# Microcontroller.net
KiCad netlist of a schematic drawn in Altium Designer
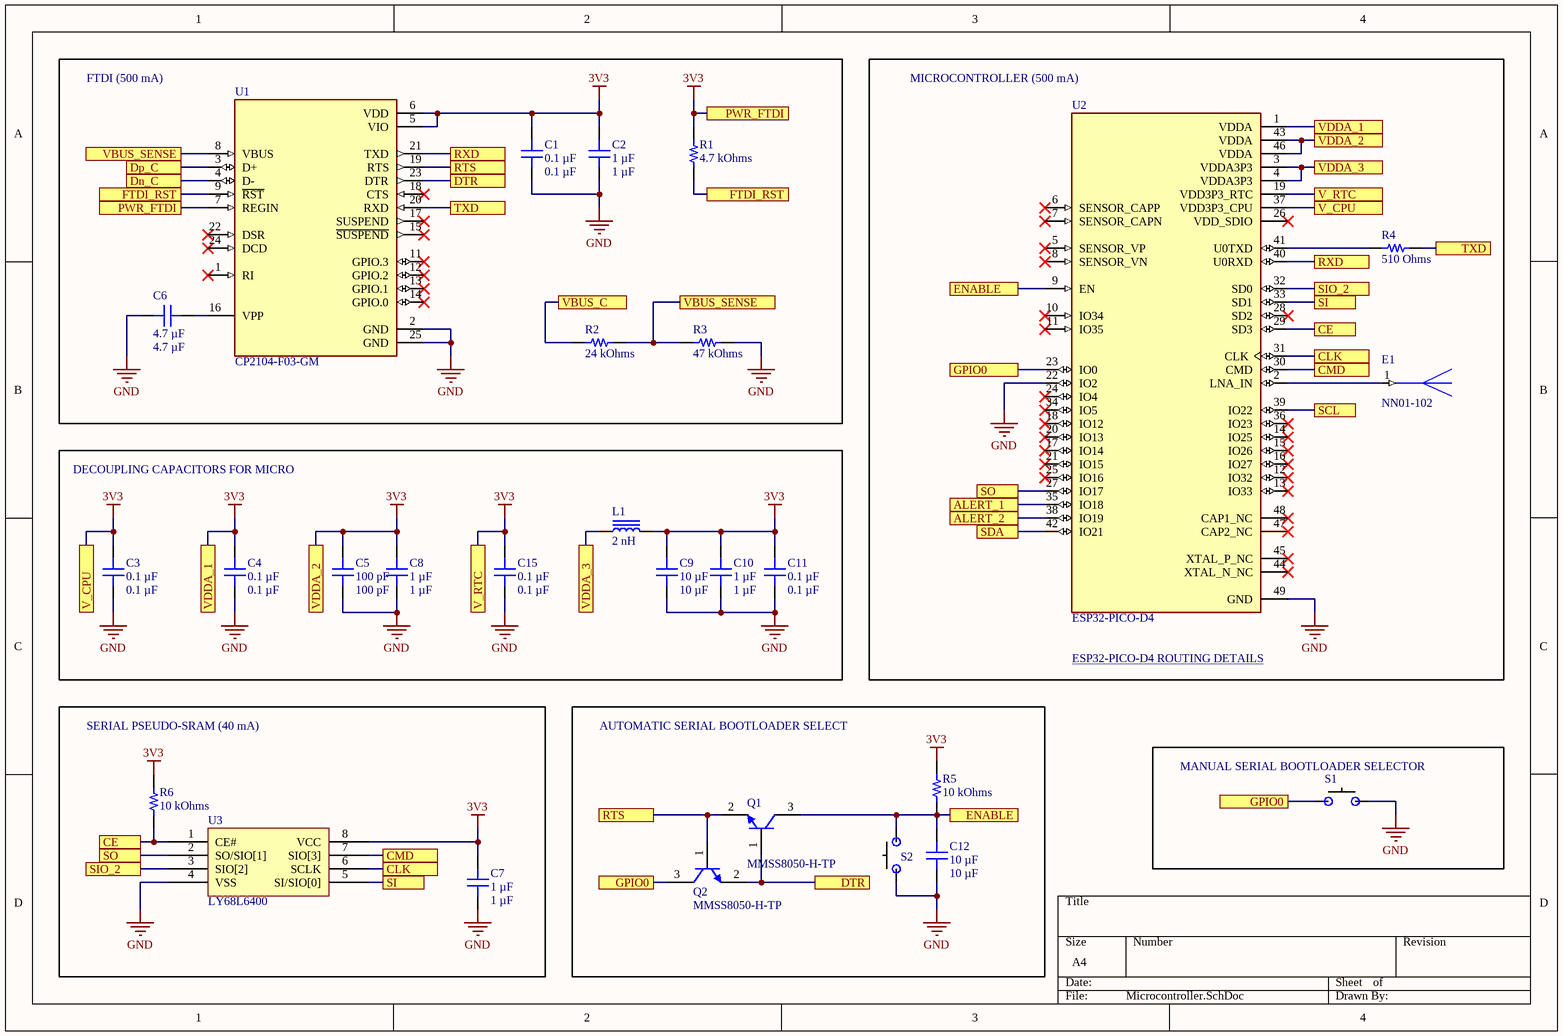
[diagram p0: Microcontroller.SchDoc]

(export (version "E")
  (design (tool "Eeschema 10.0.6"))
  (components
    (comp (ref "C1")
      (value "0.1 µF")
      (footprint "CAP 0603_1608")
      (description "CAP CER 0.1UF 50V X7R 0603")
      (fields
        (field (name "PART NUMBER") "C0603C104K5RAC7411")
        (field (name "ALTIUM_VALUE") "0.1 µF")
        (field (name "MANUFACTURER") "KEMET")
      )
      (libsource (lib "Celestial Altium Library - altium_library") (part "Capacitor"))
    )
    (comp (ref "C2")
      (value "1 µF")
      (footprint "CAP 0603_1608")
      (description "CAP CER 1UF 10V X7R 0603")
      (fields
        (field (name "PART NUMBER") "CC0603KRX7R6BB105")
        (field (name "ALTIUM_VALUE") "1 µF")
        (field (name "MANUFACTURER") "Yageo")
      )
      (libsource (lib "Celestial Altium Library - altium_library") (part "Capacitor"))
    )
    (comp (ref "C3")
      (value "0.1 µF")
      (footprint "CAP 0603_1608")
      (description "CAP CER 0.1UF 50V X7R 0603")
      (fields
        (field (name "PART NUMBER") "C0603C104K5RAC7411")
        (field (name "ALTIUM_VALUE") "0.1 µF")
        (field (name "MANUFACTURER") "KEMET")
      )
      (libsource (lib "Celestial Altium Library - altium_library") (part "Capacitor"))
    )
    (comp (ref "C4")
      (value "0.1 µF")
      (footprint "CAP 0603_1608")
      (description "CAP CER 0.1UF 50V X7R 0603")
      (fields
        (field (name "PART NUMBER") "C0603C104K5RAC7411")
        (field (name "ALTIUM_VALUE") "0.1 µF")
        (field (name "MANUFACTURER") "KEMET")
      )
      (libsource (lib "Celestial Altium Library - altium_library") (part "Capacitor"))
    )
    (comp (ref "C5")
      (value "100 pF")
      (footprint "CAP 0603_1608")
      (description "CAP CER 100PF 50V C0G/NP0 0603")
      (fields
        (field (name "PART NUMBER") "C0603C101K5GACAUTO")
        (field (name "ALTIUM_VALUE") "100 pF")
        (field (name "MANUFACTURER") "KEMET")
      )
      (libsource (lib "Celestial Altium Library - altium_library") (part "Capacitor"))
    )
    (comp (ref "C6")
      (value "4.7 µF")
      (footprint "CAP 0603_1608")
      (description "CAP CER 4.7UF 16V X7R 0603")
      (fields
        (field (name "PART NUMBER") "GRM188Z71C475KE21J")
        (field (name "ALTIUM_VALUE") "4.7 µF")
        (field (name "MANUFACTURER") "Murata Electronics")
      )
      (libsource (lib "Celestial Altium Library - altium_library") (part "Capacitor"))
    )
    (comp (ref "C7")
      (value "1 µF")
      (footprint "CAP 0603_1608")
      (description "CAP CER 1UF 10V X7R 0603")
      (fields
        (field (name "PART NUMBER") "CC0603KRX7R6BB105")
        (field (name "ALTIUM_VALUE") "1 µF")
        (field (name "MANUFACTURER") "Yageo")
      )
      (libsource (lib "Celestial Altium Library - altium_library") (part "Capacitor"))
    )
    (comp (ref "C8")
      (value "1 µF")
      (footprint "CAP 0603_1608")
      (description "CAP CER 1UF 10V X7R 0603")
      (fields
        (field (name "PART NUMBER") "CC0603KRX7R6BB105")
        (field (name "ALTIUM_VALUE") "1 µF")
        (field (name "MANUFACTURER") "Yageo")
      )
      (libsource (lib "Celestial Altium Library - altium_library") (part "Capacitor"))
    )
    (comp (ref "C9")
      (value "10 µF")
      (footprint "CAP 0805_2012")
      (description "CAP CER 10UF 6.3V X7R 0805")
      (fields
        (field (name "PART NUMBER") "CGA4J1X7R0J106K125AC")
        (field (name "ALTIUM_VALUE") "10 µF")
        (field (name "MANUFACTURER") "TDK Corporation")
      )
      (libsource (lib "Celestial Altium Library - altium_library") (part "Capacitor"))
    )
    (comp (ref "C10")
      (value "1 µF")
      (footprint "CAP 0603_1608")
      (description "CAP CER 1UF 10V X7R 0603")
      (fields
        (field (name "PART NUMBER") "CC0603KRX7R6BB105")
        (field (name "ALTIUM_VALUE") "1 µF")
        (field (name "MANUFACTURER") "Yageo")
      )
      (libsource (lib "Celestial Altium Library - altium_library") (part "Capacitor"))
    )
    (comp (ref "C11")
      (value "0.1 µF")
      (footprint "CAP 0603_1608")
      (description "CAP CER 0.1UF 50V X7R 0603")
      (fields
        (field (name "PART NUMBER") "C0603C104K5RAC7411")
        (field (name "ALTIUM_VALUE") "0.1 µF")
        (field (name "MANUFACTURER") "KEMET")
      )
      (libsource (lib "Celestial Altium Library - altium_library") (part "Capacitor"))
    )
    (comp (ref "C12")
      (value "10 µF")
      (footprint "CAP 0805_2012")
      (description "CAP CER 10UF 6.3V X7R 0805")
      (fields
        (field (name "PART NUMBER") "CGA4J1X7R0J106K125AC")
        (field (name "ALTIUM_VALUE") "10 µF")
        (field (name "MANUFACTURER") "TDK Corporation")
      )
      (libsource (lib "Celestial Altium Library - altium_library") (part "Capacitor"))
    )
    (comp (ref "C15")
      (value "0.1 µF")
      (footprint "CAP 0603_1608")
      (description "CAP CER 0.1UF 50V X7R 0603")
      (fields
        (field (name "PART NUMBER") "C0603C104K5RAC7411")
        (field (name "ALTIUM_VALUE") "0.1 µF")
        (field (name "MANUFACTURER") "KEMET")
      )
      (libsource (lib "Celestial Altium Library - altium_library") (part "Capacitor"))
    )
    (comp (ref "E1")
      (value "NN01-102")
      (footprint "NN01-102:XCVR_NN01-102")
      (description "2.45GHz Bluetooth, WLAN, Zigbee Chip RF Antenna 2.4GHz ~ 2.5GHz 1.7dBi Solder Surface Mount")
      (fields (field (name "MF") "{'manufacturer': u'Ignion'}"))
      (libsource (lib "NN01-102") (part "NN01-102"))
    )
    (comp (ref "L1")
      (value "2 nH")
      (footprint "IND 0402_1005")
      (description "FIXED IND 2NH 1A 50 MOHM SMD")
      (fields (field (name "PART NUMBER") "MHQ1005P2N0BT000") (field (name "MANUFACTURER") "TDK Corporation"))
      (libsource (lib "Celestial Altium Library - altium_library") (part "Inductor"))
    )
    (comp (ref "Q1")
      (value "MMSS8050-H-TP")
      (footprint "MCCSEMI SOT-23-3")
      (description "TRANS NPN 25V 1.5A SOT23")
      (fields (field (name "MANUFACTURER") "Micro Commercial Co"))
      (libsource (lib "Celestial Altium Library - altium_library") (part "MCCSEMI NPN SOT-23-3"))
    )
    (comp (ref "Q2")
      (value "MMSS8050-H-TP")
      (footprint "MCCSEMI SOT-23-3")
      (description "TRANS NPN 25V 1.5A SOT23")
      (fields (field (name "MANUFACTURER") "Micro Commercial Co"))
      (libsource (lib "Celestial Altium Library - altium_library") (part "MCCSEMI NPN SOT-23-3"))
    )
    (comp (ref "R1")
      (value "4.7 kOhms")
      (footprint "RES 0603_1608")
      (description "RES SMD 4.7K OHM 1% 1/10W 0603")
      (fields (field (name "PART NUMBER") "RT0603FRE074K7L") (field (name "MANUFACTURER") "Yageo"))
      (libsource (lib "Celestial Altium Library - altium_library") (part "Resistor"))
    )
    (comp (ref "R2")
      (value "24 kOhms")
      (footprint "RES 0603_1608")
      (description "RES 24K OHM 1% 1/10W 0603")
      (fields
        (field (name "PART NUMBER") "RK73H1JTTD2402F")
        (field (name "MANUFACTURER") "KOA Speer Electronics, Inc.")
      )
      (libsource (lib "Celestial Altium Library - altium_library") (part "Resistor"))
    )
    (comp (ref "R3")
      (value "47 kOhms")
      (footprint "RES 0603_1608")
      (description "RES SMD 47K OHM 1% 1/10W 0603")
      (fields (field (name "PART NUMBER") "RT0603FRE0747KL") (field (name "MANUFACTURER") "Yageo"))
      (libsource (lib "Celestial Altium Library - altium_library") (part "Resistor"))
    )
    (comp (ref "R4")
      (value "510 Ohms")
      (footprint "RES 0603_1608")
      (description "RES 510 OHM 5% 1/10W 0603")
      (fields
        (field (name "PART NUMBER") "RMCF0603JT510R")
        (field (name "MANUFACTURER") "Stackpole Electronics Inc")
      )
      (libsource (lib "Celestial Altium Library - altium_library") (part "Resistor"))
    )
    (comp (ref "R5")
      (value "10 kOhms")
      (footprint "RES 0603_1608")
      (description "RES SMD 10K OHM 5% 1/4W 0603")
      (fields (field (name "PART NUMBER") "RCS060310K0JNEA") (field (name "MANUFACTURER") "Vishay Dale"))
      (libsource (lib "Celestial Altium Library - altium_library") (part "Resistor"))
    )
    (comp (ref "R6")
      (value "10 kOhms")
      (footprint "RES 0603_1608")
      (description "RES SMD 10K OHM 5% 1/4W 0603")
      (fields (field (name "PART NUMBER") "RCS060310K0JNEA") (field (name "MANUFACTURER") "Vishay Dale"))
      (libsource (lib "Celestial Altium Library - altium_library") (part "Resistor"))
    )
    (comp (ref "S1")
      (value "GT-TC029B-H025-L1N")
      (footprint "GT-TC029B-H025-L1N")
      (libsource (lib "Schlib2") (part "GT-TC029B-H025-L1N"))
    )
    (comp (ref "S2")
      (value "GT-TC029B-H025-L1N")
      (footprint "GT-TC029B-H025-L1N")
      (libsource (lib "Schlib2") (part "GT-TC029B-H025-L1N"))
    )
    (comp (ref "U1")
      (value "CP2104-F03-GM")
      (footprint "CP2104-F03-GM:QFN50P400X400X80-25N")
      (description "USB-to-UART 1-CH 576byte FIFO 3.3V 24-Pin QFN EP T/R")
      (fields (field (name "MF") "{'manufacturer': u'Silicon Labs'}"))
      (libsource (lib "CP2104-F03-GM") (part "CP2104-F03-GM"))
    )
    (comp (ref "U2")
      (value "ESP32-PICO-D4")
      (footprint "ESP32-PICO-D4:PQFN50P700X700X104-49N")
      (fields (field (name "MF") "{'manufacturer': u'Espressif Systems'}"))
      (libsource (lib "ESP32-PICO-D4") (part "ESP32-PICO-D4"))
    )
    (comp (ref "U3")
      (value "LY68L6400")
      (footprint "SOP-8_3.9x4.9x1.27P")
      (description "64M Bits Serial Pseudo-SRAM with SPI and QPI")
      (libsource (lib "Power_Measurement") (part "LY68L6400SLIT"))
    )
  )
  (nets
    (net (code "1") (name "/ALERT_1") (class "Default")
      (node (ref "U2") (pin "35") (pinfunction "IO18_35") (pintype "bidirectional"))
    )
    (net (code "2") (name "/ALERT_2") (class "Default")
      (node (ref "U2") (pin "38") (pinfunction "IO19_38") (pintype "bidirectional"))
    )
    (net (code "3") (name "/CE") (class "Default")
      (node (ref "R6") (pin "2") (pinfunction "2_2") (pintype "passive"))
      (node (ref "U2") (pin "29") (pinfunction "SD3_29") (pintype "bidirectional"))
      (node (ref "U3") (pin "1") (pinfunction "CE#_1") (pintype "passive"))
    )
    (net (code "4") (name "/CLK") (class "Default")
      (node (ref "U2") (pin "31") (pinfunction "CLK_31") (pintype "bidirectional"))
      (node (ref "U3") (pin "6") (pinfunction "SCLK_6") (pintype "passive"))
    )
    (net (code "5") (name "/CMD") (class "Default")
      (node (ref "U2") (pin "30") (pinfunction "CMD_30") (pintype "bidirectional"))
      (node (ref "U3") (pin "7") (pinfunction "SIO[3]_7") (pintype "passive"))
    )
    (net (code "6") (name "/DTR") (class "Default")
      (node (ref "Q1") (pin "1") (pinfunction "B_1") (pintype "passive"))
      (node (ref "Q2") (pin "2") (pinfunction "E_2") (pintype "passive"))
      (node (ref "U1") (pin "23") (pinfunction "DTR_23") (pintype "output"))
    )
    (net (code "7") (name "/Dn_C") (class "Default")
      (node (ref "U1") (pin "4") (pinfunction "D-_4") (pintype "bidirectional"))
    )
    (net (code "8") (name "/Dp_C") (class "Default")
      (node (ref "U1") (pin "3") (pinfunction "D+_3") (pintype "bidirectional"))
    )
    (net (code "9") (name "/ENABLE") (class "Default")
      (node (ref "C12") (pin "2") (pinfunction "2_2") (pintype "passive"))
      (node (ref "Q1") (pin "3") (pinfunction "C_3") (pintype "passive"))
      (node (ref "R5") (pin "2") (pinfunction "2_2") (pintype "passive"))
      (node (ref "S2") (pin "2") (pinfunction "2_2") (pintype "passive"))
      (node (ref "U2") (pin "9") (pinfunction "EN_9") (pintype "input"))
    )
    (net (code "10") (name "/FTDI_RST") (class "Default")
      (node (ref "R1") (pin "1") (pinfunction "1_1") (pintype "passive"))
      (node (ref "U1") (pin "9") (pinfunction "~{RST}_9") (pintype "input"))
    )
    (net (code "11") (name "/GPIO0") (class "Default")
      (node (ref "Q2") (pin "3") (pinfunction "C_3") (pintype "passive"))
      (node (ref "S1") (pin "1") (pinfunction "1_1") (pintype "passive"))
      (node (ref "U2") (pin "23") (pinfunction "IO0_23") (pintype "bidirectional"))
    )
    (net (code "12") (name "/RTS") (class "Default")
      (node (ref "Q1") (pin "2") (pinfunction "E_2") (pintype "passive"))
      (node (ref "Q2") (pin "1") (pinfunction "B_1") (pintype "passive"))
      (node (ref "U1") (pin "19") (pinfunction "RTS_19") (pintype "output"))
    )
    (net (code "13") (name "/RXD") (class "Default")
      (node (ref "U1") (pin "21") (pinfunction "TXD_21") (pintype "output"))
      (node (ref "U2") (pin "40") (pinfunction "U0RXD_40") (pintype "bidirectional"))
    )
    (net (code "14") (name "/SCL") (class "Default")
      (node (ref "U2") (pin "39") (pinfunction "IO22_39") (pintype "bidirectional"))
    )
    (net (code "15") (name "/SDA") (class "Default")
      (node (ref "U2") (pin "42") (pinfunction "IO21_42") (pintype "bidirectional"))
    )
    (net (code "16") (name "/SI") (class "Default")
      (node (ref "U2") (pin "33") (pinfunction "SD1_33") (pintype "bidirectional"))
      (node (ref "U3") (pin "5") (pinfunction "SI/SIO[0]_5") (pintype "passive"))
    )
    (net (code "17") (name "/SIO_2") (class "Default")
      (node (ref "U2") (pin "32") (pinfunction "SD0_32") (pintype "bidirectional"))
      (node (ref "U3") (pin "3") (pinfunction "SIO[2]_3") (pintype "passive"))
    )
    (net (code "18") (name "/SO") (class "Default")
      (node (ref "U2") (pin "27") (pinfunction "IO17_27") (pintype "bidirectional"))
      (node (ref "U3") (pin "2") (pinfunction "SO/SIO[1]_2") (pintype "passive"))
    )
    (net (code "19") (name "/TXD") (class "Default")
      (node (ref "R4") (pin "2") (pinfunction "2_2") (pintype "passive"))
      (node (ref "U1") (pin "20") (pinfunction "RXD_20") (pintype "input"))
    )
    (net (code "20") (name "/VBUS_C") (class "Default")
      (node (ref "R2") (pin "2") (pinfunction "2_2") (pintype "passive"))
    )
    (net (code "21") (name "/VBUS_SENSE") (class "Default")
      (node (ref "R2") (pin "1") (pinfunction "1_1") (pintype "passive"))
      (node (ref "R3") (pin "2") (pinfunction "2_2") (pintype "passive"))
      (node (ref "U1") (pin "8") (pinfunction "VBUS_8") (pintype "input"))
    )
    (net (code "22") (name "/VDDA_3") (class "Default")
      (node (ref "L1") (pin "1") (pinfunction "1_1") (pintype "passive"))
      (node (ref "U2") (pin "3") (pinfunction "VDDA3P3_3") (pintype "power_in"))
      (node (ref "U2") (pin "4") (pinfunction "VDDA3P3_4") (pintype "power_in"))
    )
    (net (code "23") (name "3V3") (class "Default")
      (node (ref "C1") (pin "2") (pinfunction "2_2") (pintype "passive"))
      (node (ref "C10") (pin "2") (pinfunction "2_2") (pintype "passive"))
      (node (ref "C11") (pin "2") (pinfunction "2_2") (pintype "passive"))
      (node (ref "C15") (pin "2") (pinfunction "2_2") (pintype "passive"))
      (node (ref "C2") (pin "1") (pinfunction "1_1") (pintype "passive"))
      (node (ref "C3") (pin "2") (pinfunction "2_2") (pintype "passive"))
      (node (ref "C4") (pin "1") (pinfunction "1_1") (pintype "passive"))
      (node (ref "C5") (pin "2") (pinfunction "2_2") (pintype "passive"))
      (node (ref "C7") (pin "1") (pinfunction "1_1") (pintype "passive"))
      (node (ref "C8") (pin "2") (pinfunction "2_2") (pintype "passive"))
      (node (ref "C9") (pin "2") (pinfunction "2_2") (pintype "passive"))
      (node (ref "L1") (pin "2") (pinfunction "2_2") (pintype "passive"))
      (node (ref "R1") (pin "2") (pinfunction "2_2") (pintype "passive"))
      (node (ref "R5") (pin "1") (pinfunction "1_1") (pintype "passive"))
      (node (ref "R6") (pin "1") (pinfunction "1_1") (pintype "passive"))
      (node (ref "U1") (pin "5") (pinfunction "VIO_5") (pintype "power_in"))
      (node (ref "U1") (pin "6") (pinfunction "VDD_6") (pintype "power_in"))
      (node (ref "U1") (pin "7") (pinfunction "REGIN_7") (pintype "input"))
      (node (ref "U2") (pin "1") (pinfunction "VDDA_1") (pintype "power_in"))
      (node (ref "U2") (pin "19") (pinfunction "VDD3P3_RTC_19") (pintype "power_in"))
      (node (ref "U2") (pin "37") (pinfunction "VDD3P3_CPU_37") (pintype "power_in"))
      (node (ref "U2") (pin "43") (pinfunction "VDDA_43") (pintype "power_in"))
      (node (ref "U2") (pin "46") (pinfunction "VDDA_46") (pintype "power_in"))
      (node (ref "U3") (pin "8") (pinfunction "VCC_8") (pintype "passive"))
    )
    (net (code "24") (name "GND") (class "Default")
      (node (ref "C1") (pin "1") (pinfunction "1_1") (pintype "passive"))
      (node (ref "C10") (pin "1") (pinfunction "1_1") (pintype "passive"))
      (node (ref "C11") (pin "1") (pinfunction "1_1") (pintype "passive"))
      (node (ref "C12") (pin "1") (pinfunction "1_1") (pintype "passive"))
      (node (ref "C15") (pin "1") (pinfunction "1_1") (pintype "passive"))
      (node (ref "C2") (pin "2") (pinfunction "2_2") (pintype "passive"))
      (node (ref "C3") (pin "1") (pinfunction "1_1") (pintype "passive"))
      (node (ref "C4") (pin "2") (pinfunction "2_2") (pintype "passive"))
      (node (ref "C5") (pin "1") (pinfunction "1_1") (pintype "passive"))
      (node (ref "C6") (pin "2") (pinfunction "2_2") (pintype "passive"))
      (node (ref "C7") (pin "2") (pinfunction "2_2") (pintype "passive"))
      (node (ref "C8") (pin "1") (pinfunction "1_1") (pintype "passive"))
      (node (ref "C9") (pin "1") (pinfunction "1_1") (pintype "passive"))
      (node (ref "R3") (pin "1") (pinfunction "1_1") (pintype "passive"))
      (node (ref "S1") (pin "2") (pinfunction "2_2") (pintype "passive"))
      (node (ref "S2") (pin "1") (pinfunction "1_1") (pintype "passive"))
      (node (ref "U1") (pin "2") (pinfunction "GND_2") (pintype "power_in"))
      (node (ref "U1") (pin "25") (pinfunction "GND_25") (pintype "power_in"))
      (node (ref "U2") (pin "22") (pinfunction "IO2_22") (pintype "bidirectional"))
      (node (ref "U2") (pin "49") (pinfunction "GND_49") (pintype "power_in"))
      (node (ref "U3") (pin "4") (pinfunction "VSS_4") (pintype "passive"))
    )
    (net (code "25") (name "Net-(U1-VPP)") (class "Default")
      (node (ref "C6") (pin "1") (pinfunction "1_1") (pintype "passive"))
      (node (ref "U1") (pin "16") (pinfunction "VPP_16") (pintype "passive"))
    )
    (net (code "26") (name "Net-(U2-LNA_IN)") (class "Default")
      (node (ref "E1") (pin "1") (pinfunction "1_1") (pintype "input"))
      (node (ref "U2") (pin "2") (pinfunction "LNA_IN_2") (pintype "bidirectional"))
    )
    (net (code "27") (name "Net-(U2-U0TXD)") (class "Default")
      (node (ref "R4") (pin "1") (pinfunction "1_1") (pintype "passive"))
      (node (ref "U2") (pin "41") (pinfunction "U0TXD_41") (pintype "bidirectional"))
    )
    (net (code "28") (name "unconnected-(U1-CTS-Pad18)") (class "Default")
      (node (ref "U1") (pin "18") (pinfunction "CTS_18") (pintype "input+no_connect"))
    )
    (net (code "29") (name "unconnected-(U1-DCD-Pad24)") (class "Default")
      (node (ref "U1") (pin "24") (pinfunction "DCD_24") (pintype "input+no_connect"))
    )
    (net (code "30") (name "unconnected-(U1-DSR-Pad22)") (class "Default")
      (node (ref "U1") (pin "22") (pinfunction "DSR_22") (pintype "input+no_connect"))
    )
    (net (code "31") (name "unconnected-(U1-GPIO.0-Pad14)") (class "Default")
      (node (ref "U1") (pin "14") (pinfunction "GPIO.0_14") (pintype "bidirectional+no_connect"))
    )
    (net (code "32") (name "unconnected-(U1-GPIO.1-Pad13)") (class "Default")
      (node (ref "U1") (pin "13") (pinfunction "GPIO.1_13") (pintype "bidirectional+no_connect"))
    )
    (net (code "33") (name "unconnected-(U1-GPIO.2-Pad12)") (class "Default")
      (node (ref "U1") (pin "12") (pinfunction "GPIO.2_12") (pintype "bidirectional+no_connect"))
    )
    (net (code "34") (name "unconnected-(U1-GPIO.3-Pad11)") (class "Default")
      (node (ref "U1") (pin "11") (pinfunction "GPIO.3_11") (pintype "bidirectional+no_connect"))
    )
    (net (code "35") (name "unconnected-(U1-RI-Pad1)") (class "Default")
      (node (ref "U1") (pin "1") (pinfunction "RI_1") (pintype "input+no_connect"))
    )
    (net (code "36") (name "unconnected-(U1-SUSPEND-Pad17)") (class "Default")
      (node (ref "U1") (pin "17") (pinfunction "SUSPEND_17") (pintype "output+no_connect"))
    )
    (net (code "37") (name "unconnected-(U1-~{SUSPEND}-Pad15)") (class "Default")
      (node (ref "U1") (pin "15") (pinfunction "~{SUSPEND}_15") (pintype "output+no_connect"))
    )
    (net (code "38") (name "unconnected-(U2-CAP1_NC-Pad48)") (class "Default")
      (node (ref "U2") (pin "48") (pinfunction "CAP1_NC_48") (pintype "passive+no_connect"))
    )
    (net (code "39") (name "unconnected-(U2-CAP2_NC-Pad47)") (class "Default")
      (node (ref "U2") (pin "47") (pinfunction "CAP2_NC_47") (pintype "passive+no_connect"))
    )
    (net (code "40") (name "unconnected-(U2-IO4-Pad24)") (class "Default")
      (node (ref "U2") (pin "24") (pinfunction "IO4_24") (pintype "bidirectional+no_connect"))
    )
    (net (code "41") (name "unconnected-(U2-IO5-Pad34)") (class "Default")
      (node (ref "U2") (pin "34") (pinfunction "IO5_34") (pintype "bidirectional+no_connect"))
    )
    (net (code "42") (name "unconnected-(U2-IO12-Pad18)") (class "Default")
      (node (ref "U2") (pin "18") (pinfunction "IO12_18") (pintype "bidirectional+no_connect"))
    )
    (net (code "43") (name "unconnected-(U2-IO13-Pad20)") (class "Default")
      (node (ref "U2") (pin "20") (pinfunction "IO13_20") (pintype "bidirectional+no_connect"))
    )
    (net (code "44") (name "unconnected-(U2-IO14-Pad17)") (class "Default")
      (node (ref "U2") (pin "17") (pinfunction "IO14_17") (pintype "bidirectional+no_connect"))
    )
    (net (code "45") (name "unconnected-(U2-IO15-Pad21)") (class "Default")
      (node (ref "U2") (pin "21") (pinfunction "IO15_21") (pintype "bidirectional+no_connect"))
    )
    (net (code "46") (name "unconnected-(U2-IO16-Pad25)") (class "Default")
      (node (ref "U2") (pin "25") (pinfunction "IO16_25") (pintype "bidirectional+no_connect"))
    )
    (net (code "47") (name "unconnected-(U2-IO23-Pad36)") (class "Default")
      (node (ref "U2") (pin "36") (pinfunction "IO23_36") (pintype "bidirectional+no_connect"))
    )
    (net (code "48") (name "unconnected-(U2-IO25-Pad14)") (class "Default")
      (node (ref "U2") (pin "14") (pinfunction "IO25_14") (pintype "bidirectional+no_connect"))
    )
    (net (code "49") (name "unconnected-(U2-IO26-Pad15)") (class "Default")
      (node (ref "U2") (pin "15") (pinfunction "IO26_15") (pintype "bidirectional+no_connect"))
    )
    (net (code "50") (name "unconnected-(U2-IO27-Pad16)") (class "Default")
      (node (ref "U2") (pin "16") (pinfunction "IO27_16") (pintype "bidirectional+no_connect"))
    )
    (net (code "51") (name "unconnected-(U2-IO32-Pad12)") (class "Default")
      (node (ref "U2") (pin "12") (pinfunction "IO32_12") (pintype "bidirectional+no_connect"))
    )
    (net (code "52") (name "unconnected-(U2-IO33-Pad13)") (class "Default")
      (node (ref "U2") (pin "13") (pinfunction "IO33_13") (pintype "bidirectional+no_connect"))
    )
    (net (code "53") (name "unconnected-(U2-IO34-Pad10)") (class "Default")
      (node (ref "U2") (pin "10") (pinfunction "IO34_10") (pintype "input+no_connect"))
    )
    (net (code "54") (name "unconnected-(U2-IO35-Pad11)") (class "Default")
      (node (ref "U2") (pin "11") (pinfunction "IO35_11") (pintype "input+no_connect"))
    )
    (net (code "55") (name "unconnected-(U2-SD2-Pad28)") (class "Default")
      (node (ref "U2") (pin "28") (pinfunction "SD2_28") (pintype "bidirectional+no_connect"))
    )
    (net (code "56") (name "unconnected-(U2-SENSOR_CAPN-Pad7)") (class "Default")
      (node (ref "U2") (pin "7") (pinfunction "SENSOR_CAPN_7") (pintype "input+no_connect"))
    )
    (net (code "57") (name "unconnected-(U2-SENSOR_CAPP-Pad6)") (class "Default")
      (node (ref "U2") (pin "6") (pinfunction "SENSOR_CAPP_6") (pintype "input+no_connect"))
    )
    (net (code "58") (name "unconnected-(U2-SENSOR_VN-Pad8)") (class "Default")
      (node (ref "U2") (pin "8") (pinfunction "SENSOR_VN_8") (pintype "input+no_connect"))
    )
    (net (code "59") (name "unconnected-(U2-SENSOR_VP-Pad5)") (class "Default")
      (node (ref "U2") (pin "5") (pinfunction "SENSOR_VP_5") (pintype "input+no_connect"))
    )
    (net (code "60") (name "unconnected-(U2-VDD_SDIO-Pad26)") (class "Default")
      (node (ref "U2") (pin "26") (pinfunction "VDD_SDIO_26") (pintype "power_in+no_connect"))
    )
    (net (code "61") (name "unconnected-(U2-XTAL_N_NC-Pad44)") (class "Default")
      (node (ref "U2") (pin "44") (pinfunction "XTAL_N_NC_44") (pintype "passive+no_connect"))
    )
    (net (code "62") (name "unconnected-(U2-XTAL_P_NC-Pad45)") (class "Default")
      (node (ref "U2") (pin "45") (pinfunction "XTAL_P_NC_45") (pintype "passive+no_connect"))
    )
  )
)
